# Stroboman.net
KiCad netlist of a schematic drawn in EAGLE
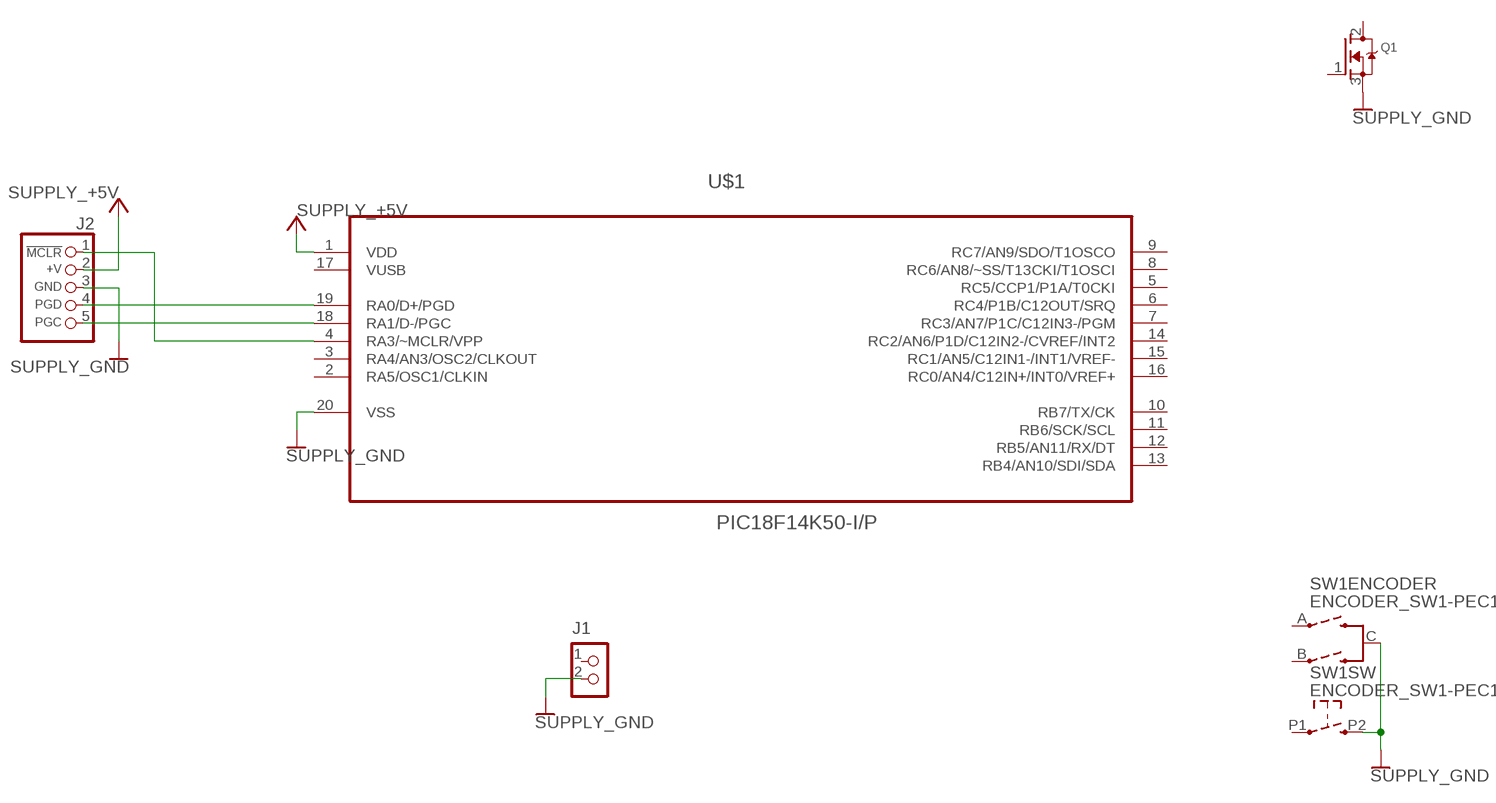
[diagram p0: schematic, sheet 1]

(export (version "E")
  (design (tool "Eeschema 10.0.6"))
  (components
    (comp (ref "J1")
      (value "CON_HEADER_1X02-PTH")
      (footprint "eagle-import:M1X2")
      (libsource (lib "eagle-import") (part "CON_HEADER_1X02-PTH"))
    )
    (comp (ref "J2")
      (value "CON_HEADER_PRG_PIC_ICSP0.1INCH_B")
      (footprint "eagle-import:HEADER_PRG_1X05_ICSP_B")
      (libsource (lib "eagle-import") (part "CON_HEADER_PRG_PIC_ICSP0.1INCH_B"))
    )
    (comp (ref "Q1")
      (value "MOSFET-NGDS_TO220V")
      (footprint "eagle-import:TO220V")
      (libsource (lib "eagle-import") (part "MOSFET-NGDS_TO220V"))
    )
    (comp (ref "SW1")
      (value "ENCODER_SW1-PEC12")
      (footprint "eagle-import:PEC12_INCREMENTAL_ENCODER")
      (libsource (lib "eagle-import") (part "ENCODER_SW1-PEC12"))
    )
    (comp (ref "U$1")
      (value "PIC18F14K50-I/P")
      (footprint "eagle-import:DIP254P762X533-20")
      (libsource (lib "eagle-import") (part "PIC18F14K50-I/P"))
    )
  )
  (nets
    (net (code "1") (name "/VUSB") (class "Default")
      (node (ref "U$1") (pin "17") (pinfunction "VUSB_17") (pintype "power_in"))
    )
    (net (code "2") (name "Net-(J2-PGC)") (class "Default")
      (node (ref "J2") (pin "5") (pinfunction "PGC_5") (pintype "passive"))
      (node (ref "U$1") (pin "18") (pinfunction "RA1/D-/PGC_18") (pintype "bidirectional"))
    )
    (net (code "3") (name "Net-(J2-PGD)") (class "Default")
      (node (ref "J2") (pin "4") (pinfunction "PGD_4") (pintype "passive"))
      (node (ref "U$1") (pin "19") (pinfunction "RA0/D+/PGD_19") (pintype "bidirectional"))
    )
    (net (code "4") (name "Net-(J2-{slash}MCLR)") (class "Default")
      (node (ref "J2") (pin "1") (pinfunction "/MCLR_1") (pintype "passive"))
      (node (ref "U$1") (pin "4") (pinfunction "RA3/~{MCLR/VPP}_4") (pintype "input"))
    )
    (net (code "5") (name "SUPPLY_+5V") (class "Default")
      (node (ref "J2") (pin "2") (pinfunction "+V_2") (pintype "passive"))
      (node (ref "U$1") (pin "1") (pinfunction "VDD_1") (pintype "power_in"))
    )
    (net (code "6") (name "SUPPLY_GND") (class "Default")
      (node (ref "J1") (pin "2") (pinfunction "2_2") (pintype "passive"))
      (node (ref "J2") (pin "3") (pinfunction "GND_3") (pintype "passive"))
      (node (ref "Q1") (pin "3") (pinfunction "S_3") (pintype "bidirectional"))
      (node (ref "SW1") (pin "C") (pinfunction "C_C") (pintype "passive"))
      (node (ref "SW1") (pin "P2") (pinfunction "2_P2") (pintype "passive"))
      (node (ref "U$1") (pin "20") (pinfunction "VSS_20") (pintype "power_in"))
    )
    (net (code "7") (name "unconnected-(J1-Pad1)") (class "Default")
      (node (ref "J1") (pin "1") (pinfunction "1_1") (pintype "passive"))
    )
    (net (code "8") (name "unconnected-(Q1-D-Pad2)") (class "Default")
      (node (ref "Q1") (pin "2") (pinfunction "D_2") (pintype "bidirectional"))
    )
    (net (code "9") (name "unconnected-(Q1-G-Pad1)") (class "Default")
      (node (ref "Q1") (pin "1") (pinfunction "G_1") (pintype "bidirectional"))
    )
    (net (code "10") (name "unconnected-(SW1-PadA)") (class "Default")
      (node (ref "SW1") (pin "A") (pinfunction "A_A") (pintype "passive"))
    )
    (net (code "11") (name "unconnected-(SW1-PadB)") (class "Default")
      (node (ref "SW1") (pin "B") (pinfunction "B_B") (pintype "passive"))
    )
    (net (code "12") (name "unconnected-(SW1B-1-PadP1)") (class "Default")
      (node (ref "SW1") (pin "P1") (pinfunction "1_P1") (pintype "passive"))
    )
    (net (code "13") (name "unconnected-(U$1-RA4{slash}AN3{slash}OSC2{slash}CLKOUT-Pad3)") (class "Default")
      (node (ref "U$1") (pin "3") (pinfunction "RA4/AN3/OSC2/CLKOUT_3") (pintype "bidirectional"))
    )
    (net (code "14") (name "unconnected-(U$1-RA5{slash}OSC1{slash}CLKIN-Pad2)") (class "Default")
      (node (ref "U$1") (pin "2") (pinfunction "RA5/OSC1/CLKIN_2") (pintype "bidirectional"))
    )
    (net (code "15") (name "unconnected-(U$1-RB4{slash}AN10{slash}SDI{slash}SDA-Pad13)") (class "Default")
      (node (ref "U$1") (pin "13") (pinfunction "RB4/AN10/SDI/SDA_13") (pintype "bidirectional"))
    )
    (net (code "16") (name "unconnected-(U$1-RB5{slash}AN11{slash}RX{slash}DT-Pad12)") (class "Default")
      (node (ref "U$1") (pin "12") (pinfunction "RB5/AN11/RX/DT_12") (pintype "bidirectional"))
    )
    (net (code "17") (name "unconnected-(U$1-RB6{slash}SCK{slash}SCL-Pad11)") (class "Default")
      (node (ref "U$1") (pin "11") (pinfunction "RB6/SCK/SCL_11") (pintype "bidirectional"))
    )
    (net (code "18") (name "unconnected-(U$1-RB7{slash}TX{slash}CK-Pad10)") (class "Default")
      (node (ref "U$1") (pin "10") (pinfunction "RB7/TX/CK_10") (pintype "bidirectional"))
    )
    (net (code "19") (name "unconnected-(U$1-RC0{slash}AN4{slash}C12IN+{slash}INT0{slash}VREF+-Pad16)") (class "Default")
      (node (ref "U$1") (pin "16") (pinfunction "RC0/AN4/C12IN+/INT0/VREF+_16") (pintype "bidirectional"))
    )
    (net (code "20") (name "unconnected-(U$1-RC1{slash}AN5{slash}C12IN1-{slash}INT1{slash}VREF--Pad15)") (class "Default")
      (node (ref "U$1") (pin "15") (pinfunction "RC1/AN5/C12IN1-/INT1/VREF-_15") (pintype "bidirectional"))
    )
    (net (code "21") (name "unconnected-(U$1-RC2{slash}AN6{slash}P1D{slash}C12IN2-{slash}CVREF{slash}INT2-Pad14)") (class "Default")
      (node (ref "U$1") (pin "14") (pinfunction "RC2/AN6/P1D/C12IN2-/CVREF/INT2_14") (pintype "bidirectional"))
    )
    (net (code "22") (name "unconnected-(U$1-RC3{slash}AN7{slash}P1C{slash}C12IN3-{slash}PGM-Pad7)") (class "Default")
      (node (ref "U$1") (pin "7") (pinfunction "RC3/AN7/P1C/C12IN3-/PGM_7") (pintype "bidirectional"))
    )
    (net (code "23") (name "unconnected-(U$1-RC4{slash}P1B{slash}C12OUT{slash}SRQ-Pad6)") (class "Default")
      (node (ref "U$1") (pin "6") (pinfunction "RC4/P1B/C12OUT/SRQ_6") (pintype "bidirectional"))
    )
    (net (code "24") (name "unconnected-(U$1-RC5{slash}CCP1{slash}P1A{slash}T0CKI-Pad5)") (class "Default")
      (node (ref "U$1") (pin "5") (pinfunction "RC5/CCP1/P1A/T0CKI_5") (pintype "bidirectional"))
    )
    (net (code "25") (name "unconnected-(U$1-RC6{slash}AN8{slash}~{SS{slash}T13CKI{slash}T1OSCI}-Pad8)") (class "Default")
      (node (ref "U$1") (pin "8") (pinfunction "RC6/AN8/~{SS/T13CKI/T1OSCI}_8") (pintype "bidirectional"))
    )
    (net (code "26") (name "unconnected-(U$1-RC7{slash}AN9{slash}SDO{slash}T1OSCO-Pad9)") (class "Default")
      (node (ref "U$1") (pin "9") (pinfunction "RC7/AN9/SDO/T1OSCO_9") (pintype "bidirectional"))
    )
  )
)
